# Main.net
KiCad netlist of a schematic drawn in EAGLE
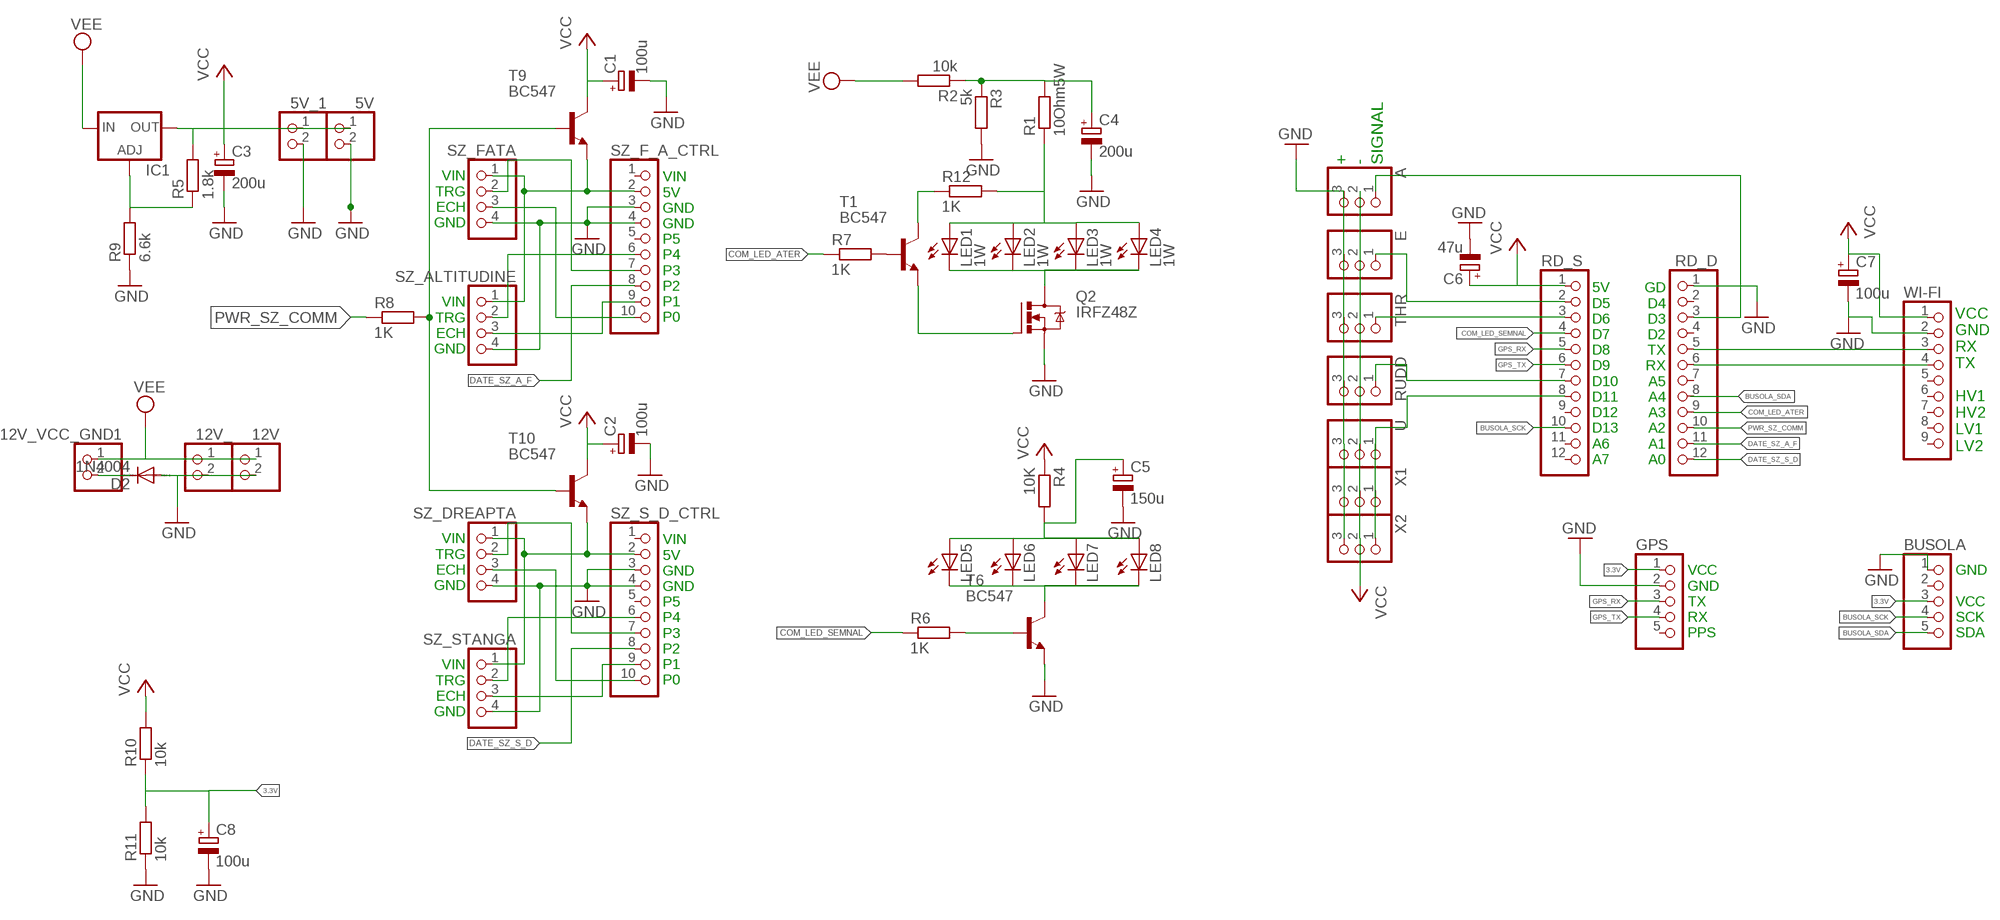
[diagram p0: schematic, sheet 1]

(export (version "E")
  (design (tool "Eeschema 10.0.6"))
  (components
    (comp (ref "5V")
      (value "PINHD-1X2")
      (footprint "eagle-import:1X02")
      (libsource (lib "eagle-import") (part "PINHD-1X2"))
    )
    (comp (ref "5V_1")
      (value "PINHD-1X2")
      (footprint "eagle-import:1X02")
      (libsource (lib "eagle-import") (part "PINHD-1X2"))
    )
    (comp (ref "12V")
      (value "PINHD-1X2")
      (footprint "eagle-import:1X02")
      (libsource (lib "eagle-import") (part "PINHD-1X2"))
    )
    (comp (ref "12V_")
      (value "PINHD-1X2")
      (footprint "eagle-import:1X02")
      (libsource (lib "eagle-import") (part "PINHD-1X2"))
    )
    (comp (ref "12V_VCC_GND1")
      (value "PINHD-1X2")
      (footprint "eagle-import:1X02")
      (libsource (lib "eagle-import") (part "PINHD-1X2"))
    )
    (comp (ref "A")
      (value "PINHD-1X3/90")
      (footprint "eagle-import:1X03_90")
      (libsource (lib "eagle-import") (part "PINHD-1X3/90"))
    )
    (comp (ref "BUSOLA")
      (value "PINHD-1X5")
      (footprint "eagle-import:1X05")
      (libsource (lib "eagle-import") (part "PINHD-1X5"))
    )
    (comp (ref "C1")
      (value "100u")
      (footprint "eagle-import:E2-5")
      (libsource (lib "eagle-import") (part "CPOL-EUE2-5"))
    )
    (comp (ref "C2")
      (value "100u")
      (footprint "eagle-import:E2-5")
      (libsource (lib "eagle-import") (part "CPOL-EUE2-5"))
    )
    (comp (ref "C3")
      (value "200u")
      (footprint "eagle-import:E2-5")
      (libsource (lib "eagle-import") (part "CPOL-EUE2-5"))
    )
    (comp (ref "C4")
      (value "200u")
      (footprint "eagle-import:E2-5")
      (libsource (lib "eagle-import") (part "CPOL-EUE2-5"))
    )
    (comp (ref "C5")
      (value "150u")
      (footprint "eagle-import:E2-5")
      (libsource (lib "eagle-import") (part "CPOL-EUE2-5"))
    )
    (comp (ref "C6")
      (value "47u")
      (footprint "eagle-import:E2-5")
      (libsource (lib "eagle-import") (part "CPOL-EUE2-5"))
    )
    (comp (ref "C7")
      (value "100u")
      (footprint "eagle-import:E2-5")
      (libsource (lib "eagle-import") (part "CPOL-EUE2-5"))
    )
    (comp (ref "C8")
      (value "100u")
      (footprint "eagle-import:E2-5")
      (libsource (lib "eagle-import") (part "CPOL-EUE2-5"))
    )
    (comp (ref "D2")
      (value "1N4004")
      (footprint "eagle-import:DO41-10")
      (libsource (lib "eagle-import") (part "1N4004"))
    )
    (comp (ref "E")
      (value "PINHD-1X3/90")
      (footprint "eagle-import:1X03_90")
      (libsource (lib "eagle-import") (part "PINHD-1X3/90"))
    )
    (comp (ref "GPS")
      (value "PINHD-1X5")
      (footprint "eagle-import:1X05")
      (libsource (lib "eagle-import") (part "PINHD-1X5"))
    )
    (comp (ref "IC1")
      (value "LM317TL")
      (footprint "eagle-import:317TL")
      (libsource (lib "eagle-import") (part "LM317TL"))
    )
    (comp (ref "LED1")
      (value "1W")
      (footprint "eagle-import:OSRAM-SIDELED")
      (libsource (lib "eagle-import") (part "LEDSIDELED"))
    )
    (comp (ref "LED2")
      (value "1W")
      (footprint "eagle-import:OSRAM-SIDELED")
      (libsource (lib "eagle-import") (part "LEDSIDELED"))
    )
    (comp (ref "LED3")
      (value "1W")
      (footprint "eagle-import:OSRAM-SIDELED")
      (libsource (lib "eagle-import") (part "LEDSIDELED"))
    )
    (comp (ref "LED4")
      (value "1W")
      (footprint "eagle-import:OSRAM-SIDELED")
      (libsource (lib "eagle-import") (part "LEDSIDELED"))
    )
    (comp (ref "LED5")
      (value "LED5MM")
      (footprint "eagle-import:LED5MM")
      (libsource (lib "eagle-import") (part "LED5MM"))
    )
    (comp (ref "LED6")
      (value "LED5MM")
      (footprint "eagle-import:LED5MM")
      (libsource (lib "eagle-import") (part "LED5MM"))
    )
    (comp (ref "LED7")
      (value "LED5MM")
      (footprint "eagle-import:LED5MM")
      (libsource (lib "eagle-import") (part "LED5MM"))
    )
    (comp (ref "LED8")
      (value "LED5MM")
      (footprint "eagle-import:LED5MM")
      (libsource (lib "eagle-import") (part "LED5MM"))
    )
    (comp (ref "Q2")
      (value "IRFZ48Z")
      (footprint "eagle-import:TO220BH")
      (libsource (lib "eagle-import") (part "IRFZ48Z"))
    )
    (comp (ref "R1")
      (value "10Ohm5W")
      (footprint "eagle-import:0309_12")
      (libsource (lib "eagle-import") (part "R-EU_0309/12"))
    )
    (comp (ref "R2")
      (value "10k")
      (footprint "eagle-import:0309_12")
      (libsource (lib "eagle-import") (part "R-EU_0309/12"))
    )
    (comp (ref "R3")
      (value "5k")
      (footprint "eagle-import:0309_12")
      (libsource (lib "eagle-import") (part "R-EU_0309/12"))
    )
    (comp (ref "R4")
      (value "10K")
      (footprint "eagle-import:0309_12")
      (libsource (lib "eagle-import") (part "R-EU_0309/12"))
    )
    (comp (ref "R5")
      (value "1.8k")
      (footprint "eagle-import:0309_12")
      (libsource (lib "eagle-import") (part "R-EU_0309/12"))
    )
    (comp (ref "R6")
      (value "1K")
      (footprint "eagle-import:0309_12")
      (libsource (lib "eagle-import") (part "R-EU_0309/12"))
    )
    (comp (ref "R7")
      (value "1K")
      (footprint "eagle-import:0309_12")
      (libsource (lib "eagle-import") (part "R-EU_0309/12"))
    )
    (comp (ref "R8")
      (value "1K")
      (footprint "eagle-import:0309_12")
      (libsource (lib "eagle-import") (part "R-EU_0309/12"))
    )
    (comp (ref "R9")
      (value "6.6k")
      (footprint "eagle-import:0309_12")
      (libsource (lib "eagle-import") (part "R-EU_0309/12"))
    )
    (comp (ref "R10")
      (value "10k")
      (footprint "eagle-import:0309_12")
      (libsource (lib "eagle-import") (part "R-EU_0309/12"))
    )
    (comp (ref "R11")
      (value "10k")
      (footprint "eagle-import:0309_12")
      (libsource (lib "eagle-import") (part "R-EU_0309/12"))
    )
    (comp (ref "R12")
      (value "1K")
      (footprint "eagle-import:0309_12")
      (libsource (lib "eagle-import") (part "R-EU_0309/12"))
    )
    (comp (ref "RD_D")
      (value "PINHD-1X12")
      (footprint "eagle-import:1X12")
      (libsource (lib "eagle-import") (part "PINHD-1X12"))
    )
    (comp (ref "RD_S")
      (value "PINHD-1X12")
      (footprint "eagle-import:1X12")
      (libsource (lib "eagle-import") (part "PINHD-1X12"))
    )
    (comp (ref "RUDD")
      (value "PINHD-1X3/90")
      (footprint "eagle-import:1X03_90")
      (libsource (lib "eagle-import") (part "PINHD-1X3/90"))
    )
    (comp (ref "SZ_ALTITUDINE")
      (value "PINHD-1X4")
      (footprint "eagle-import:1X04")
      (libsource (lib "eagle-import") (part "PINHD-1X4"))
    )
    (comp (ref "SZ_DREAPTA")
      (value "PINHD-1X4")
      (footprint "eagle-import:1X04")
      (libsource (lib "eagle-import") (part "PINHD-1X4"))
    )
    (comp (ref "SZ_FATA")
      (value "PINHD-1X4")
      (footprint "eagle-import:1X04")
      (libsource (lib "eagle-import") (part "PINHD-1X4"))
    )
    (comp (ref "SZ_F_A_CTRL")
      (value "PINHD-1X10")
      (footprint "eagle-import:1X10")
      (libsource (lib "eagle-import") (part "PINHD-1X10"))
    )
    (comp (ref "SZ_STANGA")
      (value "PINHD-1X4")
      (footprint "eagle-import:1X04")
      (libsource (lib "eagle-import") (part "PINHD-1X4"))
    )
    (comp (ref "SZ_S_D_CTRL")
      (value "PINHD-1X10")
      (footprint "eagle-import:1X10")
      (libsource (lib "eagle-import") (part "PINHD-1X10"))
    )
    (comp (ref "T1")
      (value "BC547")
      (footprint "eagle-import:TO92")
      (libsource (lib "eagle-import") (part "BC547"))
    )
    (comp (ref "T6")
      (value "BC547")
      (footprint "eagle-import:TO92")
      (libsource (lib "eagle-import") (part "BC547"))
    )
    (comp (ref "T9")
      (value "BC547")
      (footprint "eagle-import:TO92")
      (libsource (lib "eagle-import") (part "BC547"))
    )
    (comp (ref "T10")
      (value "BC547")
      (footprint "eagle-import:TO92")
      (libsource (lib "eagle-import") (part "BC547"))
    )
    (comp (ref "THR")
      (value "PINHD-1X3/90")
      (footprint "eagle-import:1X03_90")
      (libsource (lib "eagle-import") (part "PINHD-1X3/90"))
    )
    (comp (ref "U")
      (value "PINHD-1X3/90")
      (footprint "eagle-import:1X03_90")
      (libsource (lib "eagle-import") (part "PINHD-1X3/90"))
    )
    (comp (ref "WI-FI")
      (value "PINHD-1X9")
      (footprint "eagle-import:1X09")
      (libsource (lib "eagle-import") (part "PINHD-1X9"))
    )
    (comp (ref "X1")
      (value "PINHD-1X3/90")
      (footprint "eagle-import:1X03_90")
      (libsource (lib "eagle-import") (part "PINHD-1X3/90"))
    )
    (comp (ref "X2")
      (value "PINHD-1X3/90")
      (footprint "eagle-import:1X03_90")
      (libsource (lib "eagle-import") (part "PINHD-1X3/90"))
    )
  )
  (nets
    (net (code "1") (name "3.3V") (class "Default")
      (node (ref "BUSOLA") (pin "3") (pinfunction "3_3") (pintype "passive"))
      (node (ref "C8") (pin "+") (pinfunction "+_+") (pintype "passive"))
      (node (ref "GPS") (pin "1") (pinfunction "1_1") (pintype "passive"))
      (node (ref "R10") (pin "1") (pinfunction "1_1") (pintype "passive"))
      (node (ref "R11") (pin "2") (pinfunction "2_2") (pintype "passive"))
    )
    (net (code "2") (name "BUSOLA_SCK") (class "Default")
      (node (ref "BUSOLA") (pin "4") (pinfunction "4_4") (pintype "passive"))
      (node (ref "RD_S") (pin "10") (pinfunction "10_10") (pintype "passive"))
    )
    (net (code "3") (name "BUSOLA_SDA") (class "Default")
      (node (ref "BUSOLA") (pin "5") (pinfunction "5_5") (pintype "passive"))
      (node (ref "RD_D") (pin "8") (pinfunction "8_8") (pintype "passive"))
    )
    (net (code "4") (name "COM_LED_ATER") (class "Default")
      (node (ref "R7") (pin "1") (pinfunction "1_1") (pintype "passive"))
      (node (ref "RD_D") (pin "9") (pinfunction "9_9") (pintype "passive"))
    )
    (net (code "5") (name "COM_LED_SEMNAL") (class "Default")
      (node (ref "R6") (pin "1") (pinfunction "1_1") (pintype "passive"))
      (node (ref "RD_S") (pin "4") (pinfunction "4_4") (pintype "passive"))
    )
    (net (code "6") (name "DATE_SZ_A_F") (class "Default")
      (node (ref "RD_D") (pin "11") (pinfunction "11_11") (pintype "passive"))
      (node (ref "SZ_F_A_CTRL") (pin "8") (pinfunction "8_8") (pintype "passive"))
    )
    (net (code "7") (name "DATE_SZ_S_D") (class "Default")
      (node (ref "RD_D") (pin "12") (pinfunction "12_12") (pintype "passive"))
      (node (ref "SZ_S_D_CTRL") (pin "8") (pinfunction "8_8") (pintype "passive"))
    )
    (net (code "8") (name "GND") (class "Default")
      (node (ref "12V") (pin "2") (pinfunction "2_2") (pintype "passive"))
      (node (ref "12V_") (pin "2") (pinfunction "2_2") (pintype "passive"))
      (node (ref "5V") (pin "2") (pinfunction "2_2") (pintype "passive"))
      (node (ref "5V_1") (pin "2") (pinfunction "2_2") (pintype "passive"))
      (node (ref "A") (pin "3") (pinfunction "3_3") (pintype "passive"))
      (node (ref "BUSOLA") (pin "1") (pinfunction "1_1") (pintype "passive"))
      (node (ref "C1") (pin "-") (pinfunction "-_-") (pintype "passive"))
      (node (ref "C2") (pin "-") (pinfunction "-_-") (pintype "passive"))
      (node (ref "C3") (pin "-") (pinfunction "-_-") (pintype "passive"))
      (node (ref "C4") (pin "-") (pinfunction "-_-") (pintype "passive"))
      (node (ref "C5") (pin "-") (pinfunction "-_-") (pintype "passive"))
      (node (ref "C6") (pin "-") (pinfunction "-_-") (pintype "passive"))
      (node (ref "C7") (pin "-") (pinfunction "-_-") (pintype "passive"))
      (node (ref "C8") (pin "-") (pinfunction "-_-") (pintype "passive"))
      (node (ref "D2") (pin "A") (pinfunction "A_A") (pintype "passive"))
      (node (ref "E") (pin "3") (pinfunction "3_3") (pintype "passive"))
      (node (ref "GPS") (pin "2") (pinfunction "2_2") (pintype "passive"))
      (node (ref "Q2") (pin "S") (pinfunction "S_S") (pintype "passive"))
      (node (ref "R11") (pin "1") (pinfunction "1_1") (pintype "passive"))
      (node (ref "R3") (pin "2") (pinfunction "2_2") (pintype "passive"))
      (node (ref "R9") (pin "1") (pinfunction "1_1") (pintype "passive"))
      (node (ref "RD_D") (pin "1") (pinfunction "1_1") (pintype "passive"))
      (node (ref "RUDD") (pin "3") (pinfunction "3_3") (pintype "passive"))
      (node (ref "SZ_ALTITUDINE") (pin "4") (pinfunction "4_4") (pintype "passive"))
      (node (ref "SZ_DREAPTA") (pin "4") (pinfunction "4_4") (pintype "passive"))
      (node (ref "SZ_FATA") (pin "4") (pinfunction "4_4") (pintype "passive"))
      (node (ref "SZ_F_A_CTRL") (pin "3") (pinfunction "3_3") (pintype "passive"))
      (node (ref "SZ_F_A_CTRL") (pin "4") (pinfunction "4_4") (pintype "passive"))
      (node (ref "SZ_STANGA") (pin "4") (pinfunction "4_4") (pintype "passive"))
      (node (ref "SZ_S_D_CTRL") (pin "3") (pinfunction "3_3") (pintype "passive"))
      (node (ref "SZ_S_D_CTRL") (pin "4") (pinfunction "4_4") (pintype "passive"))
      (node (ref "T6") (pin "1") (pinfunction "E_1") (pintype "passive"))
      (node (ref "THR") (pin "3") (pinfunction "3_3") (pintype "passive"))
      (node (ref "U") (pin "3") (pinfunction "3_3") (pintype "passive"))
      (node (ref "WI-FI") (pin "2") (pinfunction "2_2") (pintype "passive"))
      (node (ref "X1") (pin "3") (pinfunction "3_3") (pintype "passive"))
      (node (ref "X2") (pin "3") (pinfunction "3_3") (pintype "passive"))
    )
    (net (code "9") (name "GPS_RX") (class "Default")
      (node (ref "GPS") (pin "3") (pinfunction "3_3") (pintype "passive"))
      (node (ref "RD_S") (pin "5") (pinfunction "5_5") (pintype "passive"))
    )
    (net (code "10") (name "GPS_TX") (class "Default")
      (node (ref "GPS") (pin "4") (pinfunction "4_4") (pintype "passive"))
      (node (ref "RD_S") (pin "6") (pinfunction "6_6") (pintype "passive"))
    )
    (net (code "11") (name "Net-(12V_VCC_GND1-Pad2)") (class "Default")
      (node (ref "12V_VCC_GND1") (pin "2") (pinfunction "2_2") (pintype "passive"))
      (node (ref "D2") (pin "C") (pinfunction "C_C") (pintype "passive"))
    )
    (net (code "12") (name "Net-(A-Pad1)") (class "Default")
      (node (ref "A") (pin "1") (pinfunction "1_1") (pintype "passive"))
      (node (ref "RD_D") (pin "3") (pinfunction "3_3") (pintype "passive"))
    )
    (net (code "13") (name "Net-(C4-Pad+)") (class "Default")
      (node (ref "C4") (pin "+") (pinfunction "+_+") (pintype "passive"))
      (node (ref "R1") (pin "2") (pinfunction "2_2") (pintype "passive"))
      (node (ref "R2") (pin "1") (pinfunction "1_1") (pintype "passive"))
      (node (ref "R3") (pin "1") (pinfunction "1_1") (pintype "passive"))
    )
    (net (code "14") (name "Net-(C5-Pad+)") (class "Default")
      (node (ref "C5") (pin "+") (pinfunction "+_+") (pintype "passive"))
      (node (ref "LED5") (pin "A") (pinfunction "A_A") (pintype "passive"))
      (node (ref "LED6") (pin "A") (pinfunction "A_A") (pintype "passive"))
      (node (ref "LED7") (pin "A") (pinfunction "A_A") (pintype "passive"))
      (node (ref "LED8") (pin "A") (pinfunction "A_A") (pintype "passive"))
      (node (ref "R4") (pin "2") (pinfunction "2_2") (pintype "passive"))
    )
    (net (code "15") (name "Net-(E-Pad1)") (class "Default")
      (node (ref "E") (pin "1") (pinfunction "1_1") (pintype "passive"))
      (node (ref "RD_S") (pin "2") (pinfunction "2_2") (pintype "passive"))
    )
    (net (code "16") (name "Net-(IC1-ADJ)") (class "Default")
      (node (ref "IC1") (pin "1") (pinfunction "ADJ_1") (pintype "input"))
      (node (ref "R5") (pin "1") (pinfunction "1_1") (pintype "passive"))
      (node (ref "R9") (pin "2") (pinfunction "2_2") (pintype "passive"))
    )
    (net (code "17") (name "Net-(LED1-PadA)") (class "Default")
      (node (ref "LED1") (pin "A") (pinfunction "A_A") (pintype "passive"))
      (node (ref "LED2") (pin "A") (pinfunction "A_A") (pintype "passive"))
      (node (ref "LED3") (pin "A") (pinfunction "A_A") (pintype "passive"))
      (node (ref "LED4") (pin "A") (pinfunction "A_A") (pintype "passive"))
      (node (ref "R1") (pin "1") (pinfunction "1_1") (pintype "passive"))
      (node (ref "R12") (pin "2") (pinfunction "2_2") (pintype "passive"))
    )
    (net (code "18") (name "Net-(LED1-PadC)") (class "Default")
      (node (ref "LED1") (pin "C") (pinfunction "C_C") (pintype "passive"))
      (node (ref "LED2") (pin "C") (pinfunction "C_C") (pintype "passive"))
      (node (ref "LED3") (pin "C") (pinfunction "C_C") (pintype "passive"))
      (node (ref "LED4") (pin "C") (pinfunction "C_C") (pintype "passive"))
      (node (ref "Q2") (pin "D") (pinfunction "D_D") (pintype "passive"))
    )
    (net (code "19") (name "Net-(LED5-C)") (class "Default")
      (node (ref "LED5") (pin "K") (pinfunction "C_K") (pintype "passive"))
      (node (ref "LED6") (pin "K") (pinfunction "C_K") (pintype "passive"))
      (node (ref "LED7") (pin "K") (pinfunction "C_K") (pintype "passive"))
      (node (ref "LED8") (pin "K") (pinfunction "C_K") (pintype "passive"))
      (node (ref "T6") (pin "3") (pinfunction "C_3") (pintype "passive"))
    )
    (net (code "20") (name "Net-(RD_D-Pad5)") (class "Default")
      (node (ref "RD_D") (pin "5") (pinfunction "5_5") (pintype "passive"))
      (node (ref "WI-FI") (pin "3") (pinfunction "3_3") (pintype "passive"))
    )
    (net (code "21") (name "Net-(RD_D-Pad6)") (class "Default")
      (node (ref "RD_D") (pin "6") (pinfunction "6_6") (pintype "passive"))
      (node (ref "WI-FI") (pin "4") (pinfunction "4_4") (pintype "passive"))
    )
    (net (code "22") (name "Net-(RD_S-Pad3)") (class "Default")
      (node (ref "RD_S") (pin "3") (pinfunction "3_3") (pintype "passive"))
      (node (ref "THR") (pin "1") (pinfunction "1_1") (pintype "passive"))
    )
    (net (code "23") (name "Net-(RD_S-Pad7)") (class "Default")
      (node (ref "RD_S") (pin "7") (pinfunction "7_7") (pintype "passive"))
      (node (ref "RUDD") (pin "1") (pinfunction "1_1") (pintype "passive"))
    )
    (net (code "24") (name "Net-(RD_S-Pad8)") (class "Default")
      (node (ref "RD_S") (pin "8") (pinfunction "8_8") (pintype "passive"))
      (node (ref "U") (pin "1") (pinfunction "1_1") (pintype "passive"))
      (node (ref "X1") (pin "1") (pinfunction "1_1") (pintype "passive"))
      (node (ref "X2") (pin "1") (pinfunction "1_1") (pintype "passive"))
    )
    (net (code "25") (name "Net-(SZ_ALTITUDINE-Pad2)") (class "Default")
      (node (ref "SZ_ALTITUDINE") (pin "2") (pinfunction "2_2") (pintype "passive"))
      (node (ref "SZ_F_A_CTRL") (pin "6") (pinfunction "6_6") (pintype "passive"))
    )
    (net (code "26") (name "Net-(SZ_ALTITUDINE-Pad3)") (class "Default")
      (node (ref "SZ_ALTITUDINE") (pin "3") (pinfunction "3_3") (pintype "passive"))
      (node (ref "SZ_F_A_CTRL") (pin "9") (pinfunction "9_9") (pintype "passive"))
    )
    (net (code "27") (name "Net-(SZ_DREAPTA-Pad2)") (class "Default")
      (node (ref "SZ_DREAPTA") (pin "2") (pinfunction "2_2") (pintype "passive"))
      (node (ref "SZ_S_D_CTRL") (pin "7") (pinfunction "7_7") (pintype "passive"))
    )
    (net (code "28") (name "Net-(SZ_DREAPTA-Pad3)") (class "Default")
      (node (ref "SZ_DREAPTA") (pin "3") (pinfunction "3_3") (pintype "passive"))
      (node (ref "SZ_S_D_CTRL") (pin "10") (pinfunction "10_10") (pintype "passive"))
    )
    (net (code "29") (name "Net-(SZ_FATA-Pad2)") (class "Default")
      (node (ref "SZ_FATA") (pin "2") (pinfunction "2_2") (pintype "passive"))
      (node (ref "SZ_F_A_CTRL") (pin "7") (pinfunction "7_7") (pintype "passive"))
    )
    (net (code "30") (name "Net-(SZ_FATA-Pad3)") (class "Default")
      (node (ref "SZ_FATA") (pin "3") (pinfunction "3_3") (pintype "passive"))
      (node (ref "SZ_F_A_CTRL") (pin "10") (pinfunction "10_10") (pintype "passive"))
    )
    (net (code "31") (name "Net-(SZ_STANGA-Pad2)") (class "Default")
      (node (ref "SZ_STANGA") (pin "2") (pinfunction "2_2") (pintype "passive"))
      (node (ref "SZ_S_D_CTRL") (pin "6") (pinfunction "6_6") (pintype "passive"))
    )
    (net (code "32") (name "Net-(SZ_STANGA-Pad3)") (class "Default")
      (node (ref "SZ_STANGA") (pin "3") (pinfunction "3_3") (pintype "passive"))
      (node (ref "SZ_S_D_CTRL") (pin "9") (pinfunction "9_9") (pintype "passive"))
    )
    (net (code "33") (name "Net-(T1-B)") (class "Default")
      (node (ref "R7") (pin "2") (pinfunction "2_2") (pintype "passive"))
      (node (ref "T1") (pin "2") (pinfunction "B_2") (pintype "passive"))
    )
    (net (code "34") (name "Net-(T1-C)") (class "Default")
      (node (ref "R12") (pin "1") (pinfunction "1_1") (pintype "passive"))
      (node (ref "T1") (pin "3") (pinfunction "C_3") (pintype "passive"))
    )
    (net (code "35") (name "Net-(T1-E)") (class "Default")
      (node (ref "Q2") (pin "G") (pinfunction "G_G") (pintype "passive"))
      (node (ref "T1") (pin "1") (pinfunction "E_1") (pintype "passive"))
    )
    (net (code "36") (name "Net-(T6-B)") (class "Default")
      (node (ref "R6") (pin "2") (pinfunction "2_2") (pintype "passive"))
      (node (ref "T6") (pin "2") (pinfunction "B_2") (pintype "passive"))
    )
    (net (code "37") (name "Net-(T9-E)") (class "Default")
      (node (ref "SZ_ALTITUDINE") (pin "1") (pinfunction "1_1") (pintype "passive"))
      (node (ref "SZ_FATA") (pin "1") (pinfunction "1_1") (pintype "passive"))
      (node (ref "SZ_F_A_CTRL") (pin "2") (pinfunction "2_2") (pintype "passive"))
      (node (ref "T9") (pin "1") (pinfunction "E_1") (pintype "passive"))
    )
    (net (code "38") (name "Net-(T10-B)") (class "Default")
      (node (ref "R8") (pin "2") (pinfunction "2_2") (pintype "passive"))
      (node (ref "T10") (pin "2") (pinfunction "B_2") (pintype "passive"))
      (node (ref "T9") (pin "2") (pinfunction "B_2") (pintype "passive"))
    )
    (net (code "39") (name "Net-(T10-E)") (class "Default")
      (node (ref "SZ_DREAPTA") (pin "1") (pinfunction "1_1") (pintype "passive"))
      (node (ref "SZ_STANGA") (pin "1") (pinfunction "1_1") (pintype "passive"))
      (node (ref "SZ_S_D_CTRL") (pin "2") (pinfunction "2_2") (pintype "passive"))
      (node (ref "T10") (pin "1") (pinfunction "E_1") (pintype "passive"))
    )
    (net (code "40") (name "PWR_SZ_COMM") (class "Default")
      (node (ref "R8") (pin "1") (pinfunction "1_1") (pintype "passive"))
      (node (ref "RD_D") (pin "10") (pinfunction "10_10") (pintype "passive"))
    )
    (net (code "41") (name "VCC") (class "Default")
      (node (ref "5V") (pin "1") (pinfunction "1_1") (pintype "passive"))
      (node (ref "5V_1") (pin "1") (pinfunction "1_1") (pintype "passive"))
      (node (ref "A") (pin "2") (pinfunction "2_2") (pintype "passive"))
      (node (ref "C1") (pin "+") (pinfunction "+_+") (pintype "passive"))
      (node (ref "C2") (pin "+") (pinfunction "+_+") (pintype "passive"))
      (node (ref "C3") (pin "+") (pinfunction "+_+") (pintype "passive"))
      (node (ref "C6") (pin "+") (pinfunction "+_+") (pintype "passive"))
      (node (ref "C7") (pin "+") (pinfunction "+_+") (pintype "passive"))
      (node (ref "E") (pin "2") (pinfunction "2_2") (pintype "passive"))
      (node (ref "IC1") (pin "2") (pinfunction "OUT_2") (pintype "passive"))
      (node (ref "R10") (pin "2") (pinfunction "2_2") (pintype "passive"))
      (node (ref "R4") (pin "1") (pinfunction "1_1") (pintype "passive"))
      (node (ref "R5") (pin "2") (pinfunction "2_2") (pintype "passive"))
      (node (ref "RD_S") (pin "1") (pinfunction "1_1") (pintype "passive"))
      (node (ref "RUDD") (pin "2") (pinfunction "2_2") (pintype "passive"))
      (node (ref "T10") (pin "3") (pinfunction "C_3") (pintype "passive"))
      (node (ref "T9") (pin "3") (pinfunction "C_3") (pintype "passive"))
      (node (ref "THR") (pin "2") (pinfunction "2_2") (pintype "passive"))
      (node (ref "U") (pin "2") (pinfunction "2_2") (pintype "passive"))
      (node (ref "WI-FI") (pin "1") (pinfunction "1_1") (pintype "passive"))
      (node (ref "X1") (pin "2") (pinfunction "2_2") (pintype "passive"))
      (node (ref "X2") (pin "2") (pinfunction "2_2") (pintype "passive"))
    )
    (net (code "42") (name "VEE") (class "Default")
      (node (ref "12V") (pin "1") (pinfunction "1_1") (pintype "passive"))
      (node (ref "12V_") (pin "1") (pinfunction "1_1") (pintype "passive"))
      (node (ref "12V_VCC_GND1") (pin "1") (pinfunction "1_1") (pintype "passive"))
      (node (ref "IC1") (pin "3") (pinfunction "IN_3") (pintype "input"))
      (node (ref "R2") (pin "2") (pinfunction "2_2") (pintype "passive"))
    )
    (net (code "43") (name "unconnected-(BUSOLA-Pad2)") (class "Default")
      (node (ref "BUSOLA") (pin "2") (pinfunction "2_2") (pintype "passive"))
    )
    (net (code "44") (name "unconnected-(GPS-Pad5)") (class "Default")
      (node (ref "GPS") (pin "5") (pinfunction "5_5") (pintype "passive"))
    )
    (net (code "45") (name "unconnected-(RD_D-Pad2)") (class "Default")
      (node (ref "RD_D") (pin "2") (pinfunction "2_2") (pintype "passive"))
    )
    (net (code "46") (name "unconnected-(RD_D-Pad4)") (class "Default")
      (node (ref "RD_D") (pin "4") (pinfunction "4_4") (pintype "passive"))
    )
    (net (code "47") (name "unconnected-(RD_D-Pad7)") (class "Default")
      (node (ref "RD_D") (pin "7") (pinfunction "7_7") (pintype "passive"))
    )
    (net (code "48") (name "unconnected-(RD_S-Pad9)") (class "Default")
      (node (ref "RD_S") (pin "9") (pinfunction "9_9") (pintype "passive"))
    )
    (net (code "49") (name "unconnected-(RD_S-Pad11)") (class "Default")
      (node (ref "RD_S") (pin "11") (pinfunction "11_11") (pintype "passive"))
    )
    (net (code "50") (name "unconnected-(RD_S-Pad12)") (class "Default")
      (node (ref "RD_S") (pin "12") (pinfunction "12_12") (pintype "passive"))
    )
    (net (code "51") (name "unconnected-(SZ_F_A_CTRL-Pad1)") (class "Default")
      (node (ref "SZ_F_A_CTRL") (pin "1") (pinfunction "1_1") (pintype "passive"))
    )
    (net (code "52") (name "unconnected-(SZ_F_A_CTRL-Pad5)") (class "Default")
      (node (ref "SZ_F_A_CTRL") (pin "5") (pinfunction "5_5") (pintype "passive"))
    )
    (net (code "53") (name "unconnected-(SZ_S_D_CTRL-Pad1)") (class "Default")
      (node (ref "SZ_S_D_CTRL") (pin "1") (pinfunction "1_1") (pintype "passive"))
    )
    (net (code "54") (name "unconnected-(SZ_S_D_CTRL-Pad5)") (class "Default")
      (node (ref "SZ_S_D_CTRL") (pin "5") (pinfunction "5_5") (pintype "passive"))
    )
    (net (code "55") (name "unconnected-(WI-FI-Pad5)") (class "Default")
      (node (ref "WI-FI") (pin "5") (pinfunction "5_5") (pintype "passive"))
    )
    (net (code "56") (name "unconnected-(WI-FI-Pad6)") (class "Default")
      (node (ref "WI-FI") (pin "6") (pinfunction "6_6") (pintype "passive"))
    )
    (net (code "57") (name "unconnected-(WI-FI-Pad7)") (class "Default")
      (node (ref "WI-FI") (pin "7") (pinfunction "7_7") (pintype "passive"))
    )
    (net (code "58") (name "unconnected-(WI-FI-Pad8)") (class "Default")
      (node (ref "WI-FI") (pin "8") (pinfunction "8_8") (pintype "passive"))
    )
    (net (code "59") (name "unconnected-(WI-FI-Pad9)") (class "Default")
      (node (ref "WI-FI") (pin "9") (pinfunction "9_9") (pintype "passive"))
    )
  )
)
